# Energy_Monitor.net
KiCad netlist of a schematic drawn in Altium Designer
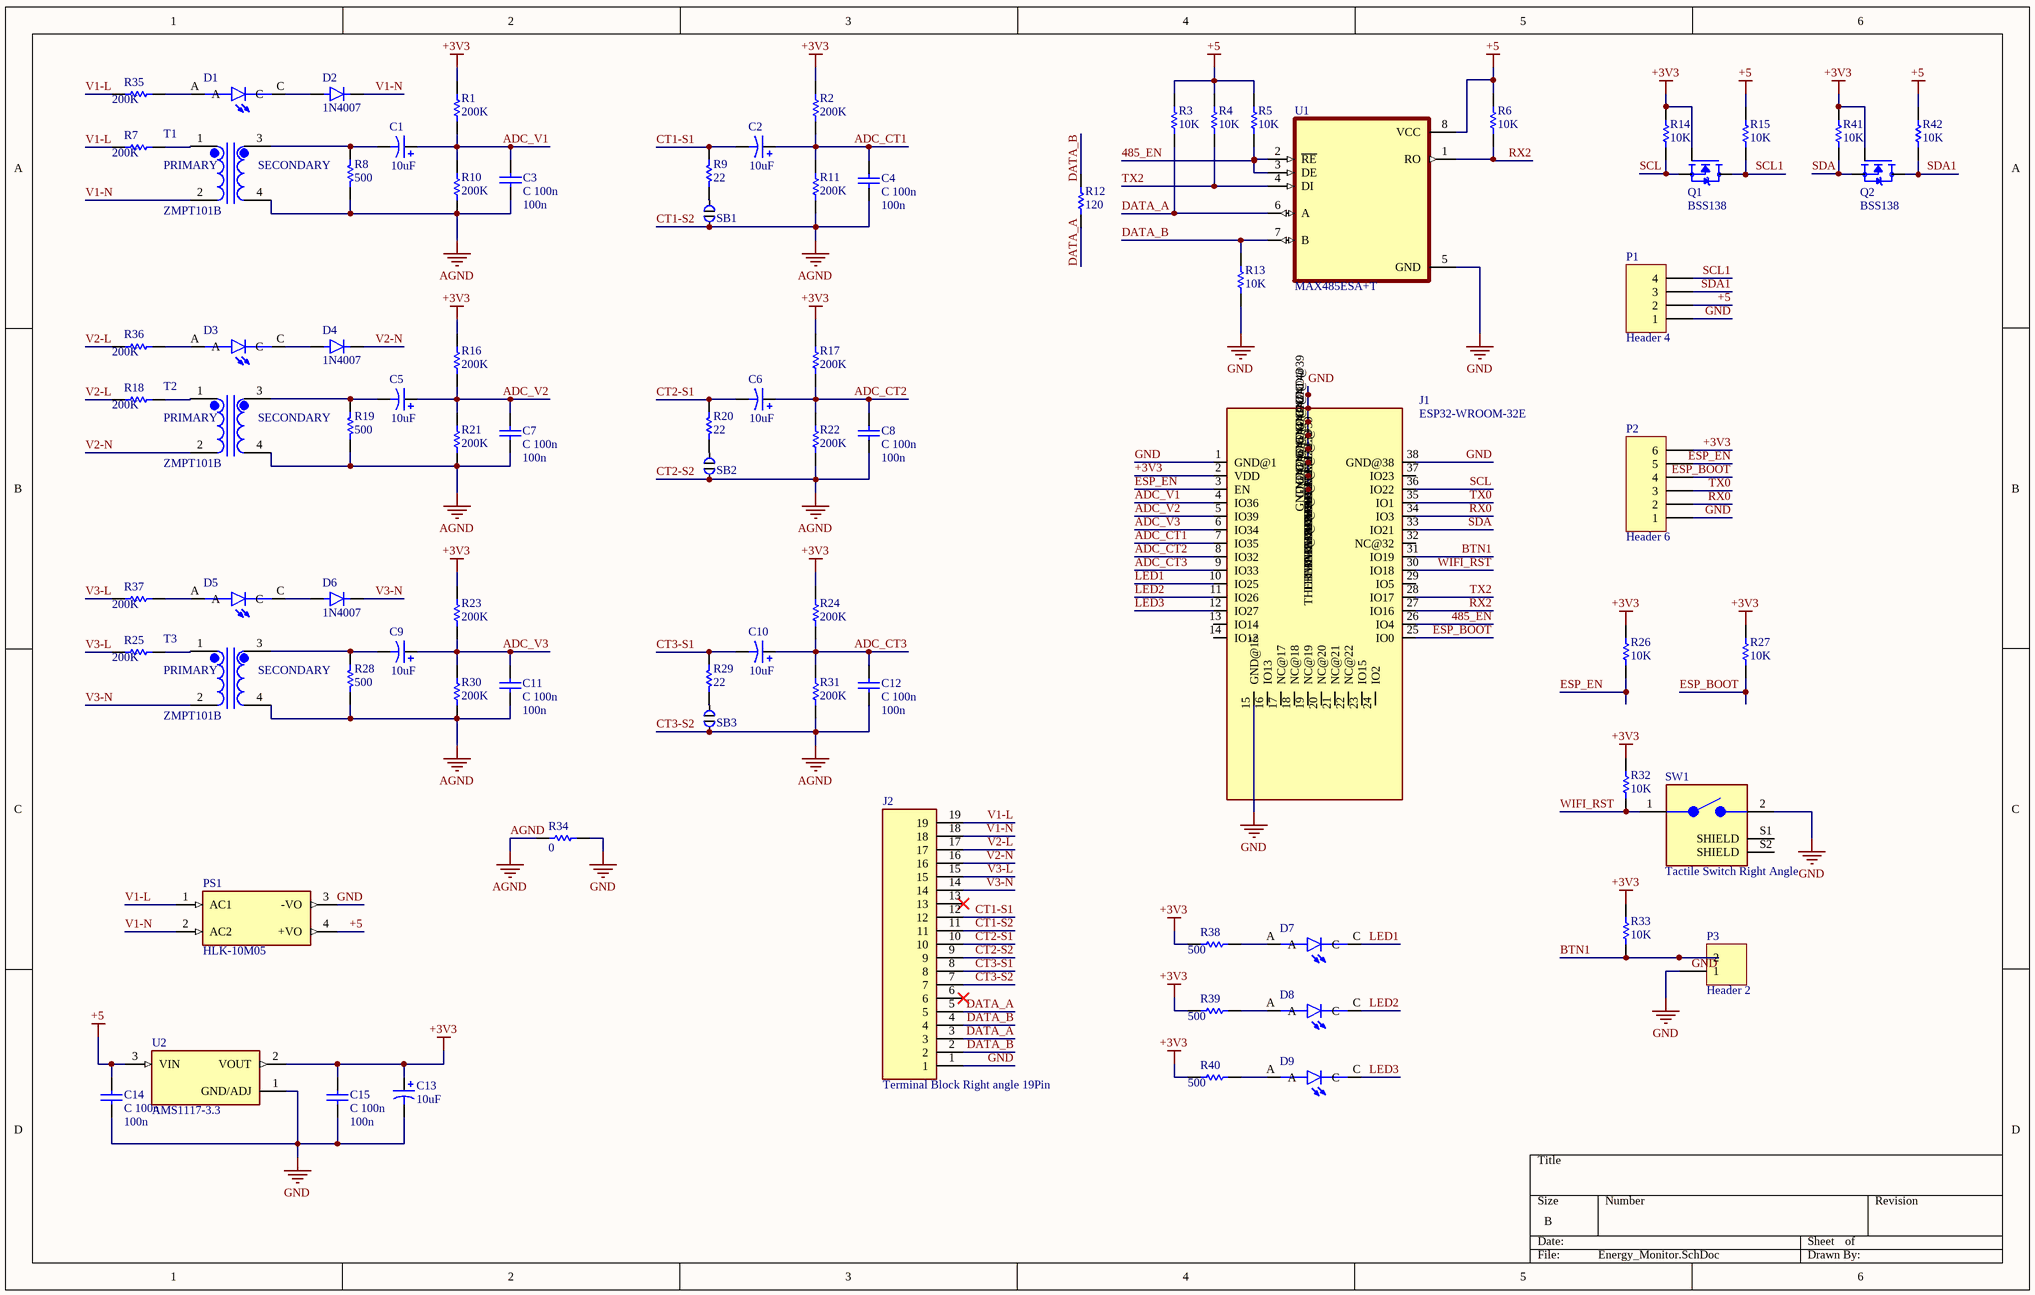
[diagram p0: Energy_Monitor.SchDoc]

(export (version "E")
  (design (tool "Eeschema 10.0.6"))
  (components
    (comp (ref "C1")
      (value "10uF")
      (footprint "C1206")
      (description "Polarized Capacitor (Radial)")
      (fields (field (name "Comment") "C Tantalum 10u") (field (name "PUBLISHER") "Altium Limited"))
      (libsource (lib "Miscellaneous Devices") (part "Cap Pol1"))
    )
    (comp (ref "C2")
      (value "10uF")
      (footprint "C1206")
      (description "Polarized Capacitor (Radial)")
      (fields (field (name "Comment") "C Tantalum 10u") (field (name "PUBLISHER") "Altium Limited"))
      (libsource (lib "Miscellaneous Devices") (part "Cap Pol1"))
    )
    (comp (ref "C3")
      (value "C 100n")
      (footprint "6-0805_N")
      (description "Capacitor")
      (fields (field (name "ALTIUM_VALUE") "100n") (field (name "PUBLISHER") "Altium Limited"))
      (libsource (lib "Miscellaneous Devices") (part "Cap"))
    )
    (comp (ref "C4")
      (value "C 100n")
      (footprint "6-0805_N")
      (description "Capacitor")
      (fields (field (name "ALTIUM_VALUE") "100n") (field (name "PUBLISHER") "Altium Limited"))
      (libsource (lib "Miscellaneous Devices") (part "Cap"))
    )
    (comp (ref "C5")
      (value "10uF")
      (footprint "C1206")
      (description "Polarized Capacitor (Radial)")
      (fields (field (name "Comment") "C Tantalum 10u") (field (name "PUBLISHER") "Altium Limited"))
      (libsource (lib "Miscellaneous Devices") (part "Cap Pol1"))
    )
    (comp (ref "C6")
      (value "10uF")
      (footprint "C1206")
      (description "Polarized Capacitor (Radial)")
      (fields (field (name "Comment") "C Tantalum 10u") (field (name "PUBLISHER") "Altium Limited"))
      (libsource (lib "Miscellaneous Devices") (part "Cap Pol1"))
    )
    (comp (ref "C7")
      (value "C 100n")
      (footprint "6-0805_N")
      (description "Capacitor")
      (fields (field (name "ALTIUM_VALUE") "100n") (field (name "PUBLISHER") "Altium Limited"))
      (libsource (lib "Miscellaneous Devices") (part "Cap"))
    )
    (comp (ref "C8")
      (value "C 100n")
      (footprint "6-0805_N")
      (description "Capacitor")
      (fields (field (name "ALTIUM_VALUE") "100n") (field (name "PUBLISHER") "Altium Limited"))
      (libsource (lib "Miscellaneous Devices") (part "Cap"))
    )
    (comp (ref "C9")
      (value "10uF")
      (footprint "C1206")
      (description "Polarized Capacitor (Radial)")
      (fields (field (name "Comment") "C Tantalum 10u") (field (name "PUBLISHER") "Altium Limited"))
      (libsource (lib "Miscellaneous Devices") (part "Cap Pol1"))
    )
    (comp (ref "C10")
      (value "10uF")
      (footprint "C1206")
      (description "Polarized Capacitor (Radial)")
      (fields (field (name "Comment") "C Tantalum 10u") (field (name "PUBLISHER") "Altium Limited"))
      (libsource (lib "Miscellaneous Devices") (part "Cap Pol1"))
    )
    (comp (ref "C11")
      (value "C 100n")
      (footprint "6-0805_N")
      (description "Capacitor")
      (fields (field (name "ALTIUM_VALUE") "100n") (field (name "PUBLISHER") "Altium Limited"))
      (libsource (lib "Miscellaneous Devices") (part "Cap"))
    )
    (comp (ref "C12")
      (value "C 100n")
      (footprint "6-0805_N")
      (description "Capacitor")
      (fields (field (name "ALTIUM_VALUE") "100n") (field (name "PUBLISHER") "Altium Limited"))
      (libsource (lib "Miscellaneous Devices") (part "Cap"))
    )
    (comp (ref "C13")
      (value "10uF")
      (footprint "C1206")
      (description "Polarized Capacitor (Radial)")
      (fields (field (name "Comment") "C Tantalum 10u") (field (name "PUBLISHER") "Altium Limited"))
      (libsource (lib "Miscellaneous Devices") (part "Cap Pol1"))
    )
    (comp (ref "C14")
      (value "C 100n")
      (footprint "6-0805_N")
      (description "Capacitor")
      (fields (field (name "ALTIUM_VALUE") "100n") (field (name "PUBLISHER") "Altium Limited"))
      (libsource (lib "Miscellaneous Devices") (part "Cap"))
    )
    (comp (ref "C15")
      (value "C 100n")
      (footprint "6-0805_N")
      (description "Capacitor")
      (fields (field (name "ALTIUM_VALUE") "100n") (field (name "PUBLISHER") "Altium Limited"))
      (libsource (lib "Miscellaneous Devices") (part "Cap"))
    )
    (comp (ref "D1")
      (value "LED 0805")
      (footprint "LEDC2012X70N")
      (description "LED Uni-Color Green 4-Pin Chip 0805 T/R")
      (fields (field (name "MP") "597-3305-607F"))
      (libsource (lib "597-3305-607F") (part "597-3305-607F"))
    )
    (comp (ref "D2")
      (value "1N4007")
      (footprint "DIOM5227X270N")
      (description "Diode Standard 1000 V 1A Surface Mount DO-214AC (SMA)")
      (fields (field (name "MF") "Diotec Semiconductor") (field (name "MP") "S1M"))
      (libsource (lib "S1M") (part "S1M"))
    )
    (comp (ref "D3")
      (value "LED 0805")
      (footprint "LEDC2012X70N")
      (description "LED Uni-Color Green 4-Pin Chip 0805 T/R")
      (fields (field (name "MP") "597-3305-607F"))
      (libsource (lib "597-3305-607F") (part "597-3305-607F"))
    )
    (comp (ref "D4")
      (value "1N4007")
      (footprint "DIOM5227X270N")
      (description "Diode Standard 1000 V 1A Surface Mount DO-214AC (SMA)")
      (fields (field (name "MF") "Diotec Semiconductor") (field (name "MP") "S1M"))
      (libsource (lib "S1M") (part "S1M"))
    )
    (comp (ref "D5")
      (value "LED 0805")
      (footprint "LEDC2012X70N")
      (description "LED Uni-Color Green 4-Pin Chip 0805 T/R")
      (fields (field (name "MP") "597-3305-607F"))
      (libsource (lib "597-3305-607F") (part "597-3305-607F"))
    )
    (comp (ref "D6")
      (value "1N4007")
      (footprint "DIOM5227X270N")
      (description "Diode Standard 1000 V 1A Surface Mount DO-214AC (SMA)")
      (fields (field (name "MF") "Diotec Semiconductor") (field (name "MP") "S1M"))
      (libsource (lib "S1M") (part "S1M"))
    )
    (comp (ref "D7")
      (value "LED 0805")
      (footprint "LEDC2012X70N")
      (description "LED Uni-Color Green 4-Pin Chip 0805 T/R")
      (fields (field (name "MP") "597-3305-607F"))
      (libsource (lib "597-3305-607F") (part "597-3305-607F"))
    )
    (comp (ref "D8")
      (value "LED 0805")
      (footprint "LEDC2012X70N")
      (description "LED Uni-Color Green 4-Pin Chip 0805 T/R")
      (fields (field (name "MP") "597-3305-607F"))
      (libsource (lib "597-3305-607F") (part "597-3305-607F"))
    )
    (comp (ref "D9")
      (value "LED 0805")
      (footprint "LEDC2012X70N")
      (description "LED Uni-Color Green 4-Pin Chip 0805 T/R")
      (fields (field (name "MP") "597-3305-607F"))
      (libsource (lib "597-3305-607F") (part "597-3305-607F"))
    )
    (comp (ref "J1")
      (value "ESP32-WROOM-32E")
      (footprint "ESP32-WROOM-32E")
      (fields (field (name "MF") "Espressif Systems"))
      (libsource (lib "ESP32-WROOM-32E") (part "ESP32-WROOM-32E"))
    )
    (comp (ref "J2")
      (value "Terminal Block Right angle 19Pin")
      (footprint "CUI_TBP01R1-508-19BE")
      (fields (field (name "MP") "TBP01R1-508-19BE"))
      (libsource (lib "TBP01R1-508-19BE") (part "TBP01R1-508-19BE"))
    )
    (comp (ref "P1")
      (value "Header 4")
      (footprint "JST_B4B-XH-A(LF)(SN)")
      (description "Header, 4-Pin")
      (fields (field (name "PUBLISHER") "Altium Limited"))
      (libsource (lib "Miscellaneous Connectors") (part "Header 4"))
    )
    (comp (ref "P2")
      (value "Header 6")
      (footprint "HDR1X6")
      (description "Header, 6-Pin")
      (fields (field (name "PUBLISHER") "Altium Limited"))
      (libsource (lib "Miscellaneous Connectors") (part "Header 6"))
    )
    (comp (ref "P3")
      (value "Header 2")
      (footprint "HDR1X2")
      (description "Header, 2-Pin")
      (fields (field (name "PUBLISHER") "Altium Limited"))
      (libsource (lib "Miscellaneous Connectors") (part "Header 2"))
    )
    (comp (ref "PS1")
      (value "HLK-10M05")
      (footprint "CONV_HLK-10M05")
      (description "10W Ultra-Compact Power Module")
      (fields (field (name "MF") "Hi-link"))
      (libsource (lib "HLK-10M05") (part "HLK-10M05"))
    )
    (comp (ref "Q1")
      (value "BSS138")
      (footprint "SOT95P240X111-3N")
      (description "N-Channel 50V 220mA (Ta) 360mW (Ta) Surface Mount SOT-23-3")
      (fields (field (name "MF") "ON Semiconductor"))
      (libsource (lib "BSS138") (part "BSS138"))
    )
    (comp (ref "Q2")
      (value "BSS138")
      (footprint "SOT95P240X111-3N")
      (description "N-Channel 50V 220mA (Ta) 360mW (Ta) Surface Mount SOT-23-3")
      (fields (field (name "MF") "ON Semiconductor"))
      (libsource (lib "BSS138") (part "BSS138"))
    )
    (comp (ref "R1")
      (value "200K")
      (footprint "6-0805_N")
      (description "Resistor")
      (fields (field (name "Comment") "R 200K") (field (name "PUBLISHER") "Altium Limited"))
      (libsource (lib "Miscellaneous Devices") (part "Res1"))
    )
    (comp (ref "R2")
      (value "200K")
      (footprint "6-0805_N")
      (description "Resistor")
      (fields (field (name "Comment") "R 200K") (field (name "PUBLISHER") "Altium Limited"))
      (libsource (lib "Miscellaneous Devices") (part "Res1"))
    )
    (comp (ref "R3")
      (value "10K")
      (footprint "6-0805_N")
      (description "Resistor")
      (fields (field (name "Comment") "R 10K") (field (name "PUBLISHER") "Altium Limited"))
      (libsource (lib "Miscellaneous Devices") (part "Res1"))
    )
    (comp (ref "R4")
      (value "10K")
      (footprint "6-0805_N")
      (description "Resistor")
      (fields (field (name "Comment") "R 10K") (field (name "PUBLISHER") "Altium Limited"))
      (libsource (lib "Miscellaneous Devices") (part "Res1"))
    )
    (comp (ref "R5")
      (value "10K")
      (footprint "6-0805_N")
      (description "Resistor")
      (fields (field (name "Comment") "R 10K") (field (name "PUBLISHER") "Altium Limited"))
      (libsource (lib "Miscellaneous Devices") (part "Res1"))
    )
    (comp (ref "R6")
      (value "10K")
      (footprint "6-0805_N")
      (description "Resistor")
      (fields (field (name "Comment") "R 10K") (field (name "PUBLISHER") "Altium Limited"))
      (libsource (lib "Miscellaneous Devices") (part "Res1"))
    )
    (comp (ref "R7")
      (value "200K")
      (footprint "6-0805_N")
      (description "Resistor")
      (fields (field (name "Comment") "R 200K") (field (name "PUBLISHER") "Altium Limited"))
      (libsource (lib "Miscellaneous Devices") (part "Res1"))
    )
    (comp (ref "R8")
      (value "500")
      (footprint "6-0805_N")
      (description "Resistor")
      (fields (field (name "Comment") "R 500") (field (name "PUBLISHER") "Altium Limited"))
      (libsource (lib "Miscellaneous Devices") (part "Res1"))
    )
    (comp (ref "R9")
      (value "22")
      (footprint "6-0805_N")
      (description "Resistor")
      (fields (field (name "Comment") "R 22") (field (name "PUBLISHER") "Altium Limited"))
      (libsource (lib "Miscellaneous Devices") (part "Res1"))
    )
    (comp (ref "R10")
      (value "200K")
      (footprint "6-0805_N")
      (description "Resistor")
      (fields (field (name "Comment") "R 200K") (field (name "PUBLISHER") "Altium Limited"))
      (libsource (lib "Miscellaneous Devices") (part "Res1"))
    )
    (comp (ref "R11")
      (value "200K")
      (footprint "6-0805_N")
      (description "Resistor")
      (fields (field (name "Comment") "R 200K") (field (name "PUBLISHER") "Altium Limited"))
      (libsource (lib "Miscellaneous Devices") (part "Res1"))
    )
    (comp (ref "R12")
      (value "120")
      (footprint "6-0805_N")
      (description "Resistor")
      (fields (field (name "Comment") "R 120") (field (name "PUBLISHER") "Altium Limited"))
      (libsource (lib "Miscellaneous Devices") (part "Res1"))
    )
    (comp (ref "R13")
      (value "10K")
      (footprint "6-0805_N")
      (description "Resistor")
      (fields (field (name "Comment") "R 10K") (field (name "PUBLISHER") "Altium Limited"))
      (libsource (lib "Miscellaneous Devices") (part "Res1"))
    )
    (comp (ref "R14")
      (value "10K")
      (footprint "6-0805_N")
      (description "Resistor")
      (fields (field (name "Comment") "R 10K") (field (name "PUBLISHER") "Altium Limited"))
      (libsource (lib "Miscellaneous Devices") (part "Res1"))
    )
    (comp (ref "R15")
      (value "10K")
      (footprint "6-0805_N")
      (description "Resistor")
      (fields (field (name "Comment") "R 10K") (field (name "PUBLISHER") "Altium Limited"))
      (libsource (lib "Miscellaneous Devices") (part "Res1"))
    )
    (comp (ref "R16")
      (value "200K")
      (footprint "6-0805_N")
      (description "Resistor")
      (fields (field (name "Comment") "R 200K") (field (name "PUBLISHER") "Altium Limited"))
      (libsource (lib "Miscellaneous Devices") (part "Res1"))
    )
    (comp (ref "R17")
      (value "200K")
      (footprint "6-0805_N")
      (description "Resistor")
      (fields (field (name "Comment") "R 200K") (field (name "PUBLISHER") "Altium Limited"))
      (libsource (lib "Miscellaneous Devices") (part "Res1"))
    )
    (comp (ref "R18")
      (value "200K")
      (footprint "6-0805_N")
      (description "Resistor")
      (fields (field (name "Comment") "R 200K") (field (name "PUBLISHER") "Altium Limited"))
      (libsource (lib "Miscellaneous Devices") (part "Res1"))
    )
    (comp (ref "R19")
      (value "500")
      (footprint "6-0805_N")
      (description "Resistor")
      (fields (field (name "Comment") "R 500") (field (name "PUBLISHER") "Altium Limited"))
      (libsource (lib "Miscellaneous Devices") (part "Res1"))
    )
    (comp (ref "R20")
      (value "22")
      (footprint "6-0805_N")
      (description "Resistor")
      (fields (field (name "Comment") "R 22") (field (name "PUBLISHER") "Altium Limited"))
      (libsource (lib "Miscellaneous Devices") (part "Res1"))
    )
    (comp (ref "R21")
      (value "200K")
      (footprint "6-0805_N")
      (description "Resistor")
      (fields (field (name "Comment") "R 200K") (field (name "PUBLISHER") "Altium Limited"))
      (libsource (lib "Miscellaneous Devices") (part "Res1"))
    )
    (comp (ref "R22")
      (value "200K")
      (footprint "6-0805_N")
      (description "Resistor")
      (fields (field (name "Comment") "R 200K") (field (name "PUBLISHER") "Altium Limited"))
      (libsource (lib "Miscellaneous Devices") (part "Res1"))
    )
    (comp (ref "R23")
      (value "200K")
      (footprint "6-0805_N")
      (description "Resistor")
      (fields (field (name "Comment") "R 200K") (field (name "PUBLISHER") "Altium Limited"))
      (libsource (lib "Miscellaneous Devices") (part "Res1"))
    )
    (comp (ref "R24")
      (value "200K")
      (footprint "6-0805_N")
      (description "Resistor")
      (fields (field (name "Comment") "R 200K") (field (name "PUBLISHER") "Altium Limited"))
      (libsource (lib "Miscellaneous Devices") (part "Res1"))
    )
    (comp (ref "R25")
      (value "200K")
      (footprint "6-0805_N")
      (description "Resistor")
      (fields (field (name "Comment") "R 200K") (field (name "PUBLISHER") "Altium Limited"))
      (libsource (lib "Miscellaneous Devices") (part "Res1"))
    )
    (comp (ref "R26")
      (value "10K")
      (footprint "6-0805_N")
      (description "Resistor")
      (fields (field (name "Comment") "R 10K") (field (name "PUBLISHER") "Altium Limited"))
      (libsource (lib "Miscellaneous Devices") (part "Res1"))
    )
    (comp (ref "R27")
      (value "10K")
      (footprint "6-0805_N")
      (description "Resistor")
      (fields (field (name "Comment") "R 10K") (field (name "PUBLISHER") "Altium Limited"))
      (libsource (lib "Miscellaneous Devices") (part "Res1"))
    )
    (comp (ref "R28")
      (value "500")
      (footprint "6-0805_N")
      (description "Resistor")
      (fields (field (name "Comment") "R 500") (field (name "PUBLISHER") "Altium Limited"))
      (libsource (lib "Miscellaneous Devices") (part "Res1"))
    )
    (comp (ref "R29")
      (value "22")
      (footprint "6-0805_N")
      (description "Resistor")
      (fields (field (name "Comment") "R 22") (field (name "PUBLISHER") "Altium Limited"))
      (libsource (lib "Miscellaneous Devices") (part "Res1"))
    )
    (comp (ref "R30")
      (value "200K")
      (footprint "6-0805_N")
      (description "Resistor")
      (fields (field (name "Comment") "R 200K") (field (name "PUBLISHER") "Altium Limited"))
      (libsource (lib "Miscellaneous Devices") (part "Res1"))
    )
    (comp (ref "R31")
      (value "200K")
      (footprint "6-0805_N")
      (description "Resistor")
      (fields (field (name "Comment") "R 200K") (field (name "PUBLISHER") "Altium Limited"))
      (libsource (lib "Miscellaneous Devices") (part "Res1"))
    )
    (comp (ref "R32")
      (value "10K")
      (footprint "6-0805_N")
      (description "Resistor")
      (fields (field (name "Comment") "R 10K") (field (name "PUBLISHER") "Altium Limited"))
      (libsource (lib "Miscellaneous Devices") (part "Res1"))
    )
    (comp (ref "R33")
      (value "10K")
      (footprint "6-0805_N")
      (description "Resistor")
      (fields (field (name "Comment") "R 10K") (field (name "PUBLISHER") "Altium Limited"))
      (libsource (lib "Miscellaneous Devices") (part "Res1"))
    )
    (comp (ref "R34")
      (value "0")
      (footprint "6-0805_N")
      (description "Resistor")
      (fields (field (name "Comment") "R 0") (field (name "PUBLISHER") "Altium Limited"))
      (libsource (lib "Miscellaneous Devices") (part "Res1"))
    )
    (comp (ref "R35")
      (value "200K")
      (footprint "6-0805_N")
      (description "Resistor")
      (fields (field (name "Comment") "R 200K") (field (name "PUBLISHER") "Altium Limited"))
      (libsource (lib "Miscellaneous Devices") (part "Res1"))
    )
    (comp (ref "R36")
      (value "200K")
      (footprint "6-0805_N")
      (description "Resistor")
      (fields (field (name "Comment") "R 200K") (field (name "PUBLISHER") "Altium Limited"))
      (libsource (lib "Miscellaneous Devices") (part "Res1"))
    )
    (comp (ref "R37")
      (value "200K")
      (footprint "6-0805_N")
      (description "Resistor")
      (fields (field (name "Comment") "R 200K") (field (name "PUBLISHER") "Altium Limited"))
      (libsource (lib "Miscellaneous Devices") (part "Res1"))
    )
    (comp (ref "R38")
      (value "500")
      (footprint "6-0805_N")
      (description "Resistor")
      (fields (field (name "Comment") "R 500") (field (name "PUBLISHER") "Altium Limited"))
      (libsource (lib "Miscellaneous Devices") (part "Res1"))
    )
    (comp (ref "R39")
      (value "500")
      (footprint "6-0805_N")
      (description "Resistor")
      (fields (field (name "Comment") "R 500") (field (name "PUBLISHER") "Altium Limited"))
      (libsource (lib "Miscellaneous Devices") (part "Res1"))
    )
    (comp (ref "R40")
      (value "500")
      (footprint "6-0805_N")
      (description "Resistor")
      (fields (field (name "Comment") "R 500") (field (name "PUBLISHER") "Altium Limited"))
      (libsource (lib "Miscellaneous Devices") (part "Res1"))
    )
    (comp (ref "R41")
      (value "10K")
      (footprint "6-0805_N")
      (description "Resistor")
      (fields (field (name "Comment") "R 10K") (field (name "PUBLISHER") "Altium Limited"))
      (libsource (lib "Miscellaneous Devices") (part "Res1"))
    )
    (comp (ref "R42")
      (value "10K")
      (footprint "6-0805_N")
      (description "Resistor")
      (fields (field (name "Comment") "R 10K") (field (name "PUBLISHER") "Altium Limited"))
      (libsource (lib "Miscellaneous Devices") (part "Res1"))
    )
    (comp (ref "SB1")
      (value "solder Bridge")
      (footprint "Solder Bridge")
      (libsource (lib "solder bridge") (part "solder Bridge"))
    )
    (comp (ref "SB2")
      (value "solder Bridge")
      (footprint "Solder Bridge")
      (libsource (lib "solder bridge") (part "solder Bridge"))
    )
    (comp (ref "SB3")
      (value "solder Bridge")
      (footprint "Solder Bridge")
      (libsource (lib "solder bridge") (part "solder Bridge"))
    )
    (comp (ref "SW1")
      (value "Tactile Switch Right Angle")
      (footprint "SW_1825027-5")
      (description "Switch Tactile OFF (ON) SPST Round Button PC Pins 0.05A 24VDC 1.57N Thru-Hole Loose Piece")
      (fields (field (name "MP") "1825027-5") (field (name "MF") "TE Connectivity"))
      (libsource (lib "1825027-5") (part "1825027-5"))
    )
    (comp (ref "T1")
      (value "ZMPT101B")
      (footprint "XFMR_ZMPT101B")
      (description "Current-type Voltage Transformer")
      (fields (field (name "MF") "Qingxian Zeming Langxi Electronic"))
      (libsource (lib "ZMPT101B") (part "ZMPT101B"))
    )
    (comp (ref "T2")
      (value "ZMPT101B")
      (footprint "XFMR_ZMPT101B")
      (description "Current-type Voltage Transformer")
      (fields (field (name "MF") "Qingxian Zeming Langxi Electronic"))
      (libsource (lib "ZMPT101B") (part "ZMPT101B"))
    )
    (comp (ref "T3")
      (value "ZMPT101B")
      (footprint "XFMR_ZMPT101B")
      (description "Current-type Voltage Transformer")
      (fields (field (name "MF") "Qingxian Zeming Langxi Electronic"))
      (libsource (lib "ZMPT101B") (part "ZMPT101B"))
    )
    (comp (ref "U1")
      (value "MAX485ESA+T")
      (footprint "SOIC127P600X175-8N")
      (description "1/1 Transceiver Half RS422, RS485 8-SOIC")
      (fields (field (name "MP") "MAX485ESA") (field (name "MF") "Maxim Integrated"))
      (libsource (lib "MAX485ESA_T") (part "MAX485ESA+T"))
    )
    (comp (ref "U2")
      (value "AMS1117-3.3")
      (footprint "SOT229P700X180-4N")
      (description "Sot223/Pkg 1-Amp 3.3-Volt Low Drop Out Voltage Regulatator")
      (fields (field (name "MF") "Advanced Monolithic Systems"))
      (libsource (lib "AMS1117-3.3") (part "AMS1117-3.3"))
    )
  )
  (nets
    (net (code "1") (name "+3V3") (class "Default")
      (node (ref "C13") (pin "1") (pinfunction "1_1") (pintype "passive"))
      (node (ref "C15") (pin "2") (pinfunction "2_2") (pintype "passive"))
      (node (ref "J1") (pin "2") (pinfunction "VDD_2") (pintype "bidirectional"))
      (node (ref "P2") (pin "6") (pinfunction "6_6") (pintype "passive"))
      (node (ref "Q1") (pin "1") (pinfunction "G_1") (pintype "passive"))
      (node (ref "Q2") (pin "1") (pinfunction "G_1") (pintype "passive"))
      (node (ref "R1") (pin "2") (pinfunction "2_2") (pintype "passive"))
      (node (ref "R14") (pin "2") (pinfunction "2_2") (pintype "passive"))
      (node (ref "R16") (pin "2") (pinfunction "2_2") (pintype "passive"))
      (node (ref "R17") (pin "2") (pinfunction "2_2") (pintype "passive"))
      (node (ref "R2") (pin "2") (pinfunction "2_2") (pintype "passive"))
      (node (ref "R23") (pin "2") (pinfunction "2_2") (pintype "passive"))
      (node (ref "R24") (pin "2") (pinfunction "2_2") (pintype "passive"))
      (node (ref "R26") (pin "2") (pinfunction "2_2") (pintype "passive"))
      (node (ref "R27") (pin "2") (pinfunction "2_2") (pintype "passive"))
      (node (ref "R32") (pin "2") (pinfunction "2_2") (pintype "passive"))
      (node (ref "R33") (pin "2") (pinfunction "2_2") (pintype "passive"))
      (node (ref "R38") (pin "1") (pinfunction "1_1") (pintype "passive"))
      (node (ref "R39") (pin "1") (pinfunction "1_1") (pintype "passive"))
      (node (ref "R40") (pin "1") (pinfunction "1_1") (pintype "passive"))
      (node (ref "R41") (pin "2") (pinfunction "2_2") (pintype "passive"))
      (node (ref "U2") (pin "2") (pinfunction "VOUT_2") (pintype "output"))
    )
    (net (code "2") (name "+5") (class "Default")
      (node (ref "C14") (pin "2") (pinfunction "2_2") (pintype "passive"))
      (node (ref "P1") (pin "2") (pinfunction "2_2") (pintype "passive"))
      (node (ref "PS1") (pin "4") (pinfunction "+VO_4") (pintype "output"))
      (node (ref "R15") (pin "2") (pinfunction "2_2") (pintype "passive"))
      (node (ref "R3") (pin "2") (pinfunction "2_2") (pintype "passive"))
      (node (ref "R4") (pin "2") (pinfunction "2_2") (pintype "passive"))
      (node (ref "R42") (pin "2") (pinfunction "2_2") (pintype "passive"))
      (node (ref "R5") (pin "2") (pinfunction "2_2") (pintype "passive"))
      (node (ref "R6") (pin "2") (pinfunction "2_2") (pintype "passive"))
      (node (ref "U1") (pin "8") (pinfunction "VCC_8") (pintype "power_in"))
      (node (ref "U2") (pin "3") (pinfunction "VIN_3") (pintype "input"))
    )
    (net (code "3") (name "/485_EN") (class "Default")
      (node (ref "J1") (pin "26") (pinfunction "IO4_26") (pintype "bidirectional"))
      (node (ref "R5") (pin "1") (pinfunction "1_1") (pintype "passive"))
      (node (ref "U1") (pin "2") (pinfunction "~{RE}_2") (pintype "input"))
      (node (ref "U1") (pin "3") (pinfunction "DE_3") (pintype "input"))
    )
    (net (code "4") (name "/ADC_CT1") (class "Default")
      (node (ref "C2") (pin "1") (pinfunction "1_1") (pintype "passive"))
      (node (ref "C4") (pin "2") (pinfunction "2_2") (pintype "passive"))
      (node (ref "J1") (pin "7") (pinfunction "IO35_7") (pintype "bidirectional"))
      (node (ref "R11") (pin "2") (pinfunction "2_2") (pintype "passive"))
      (node (ref "R2") (pin "1") (pinfunction "1_1") (pintype "passive"))
    )
    (net (code "5") (name "/ADC_CT2") (class "Default")
      (node (ref "C6") (pin "1") (pinfunction "1_1") (pintype "passive"))
      (node (ref "C8") (pin "2") (pinfunction "2_2") (pintype "passive"))
      (node (ref "J1") (pin "8") (pinfunction "IO32_8") (pintype "bidirectional"))
      (node (ref "R17") (pin "1") (pinfunction "1_1") (pintype "passive"))
      (node (ref "R22") (pin "2") (pinfunction "2_2") (pintype "passive"))
    )
    (net (code "6") (name "/ADC_CT3") (class "Default")
      (node (ref "C10") (pin "1") (pinfunction "1_1") (pintype "passive"))
      (node (ref "C12") (pin "2") (pinfunction "2_2") (pintype "passive"))
      (node (ref "J1") (pin "9") (pinfunction "IO33_9") (pintype "bidirectional"))
      (node (ref "R24") (pin "1") (pinfunction "1_1") (pintype "passive"))
      (node (ref "R31") (pin "2") (pinfunction "2_2") (pintype "passive"))
    )
    (net (code "7") (name "/ADC_V1") (class "Default")
      (node (ref "C1") (pin "1") (pinfunction "1_1") (pintype "passive"))
      (node (ref "C3") (pin "2") (pinfunction "2_2") (pintype "passive"))
      (node (ref "J1") (pin "4") (pinfunction "IO36_4") (pintype "bidirectional"))
      (node (ref "R1") (pin "1") (pinfunction "1_1") (pintype "passive"))
      (node (ref "R10") (pin "2") (pinfunction "2_2") (pintype "passive"))
    )
    (net (code "8") (name "/ADC_V2") (class "Default")
      (node (ref "C5") (pin "1") (pinfunction "1_1") (pintype "passive"))
      (node (ref "C7") (pin "2") (pinfunction "2_2") (pintype "passive"))
      (node (ref "J1") (pin "5") (pinfunction "IO39_5") (pintype "bidirectional"))
      (node (ref "R16") (pin "1") (pinfunction "1_1") (pintype "passive"))
      (node (ref "R21") (pin "2") (pinfunction "2_2") (pintype "passive"))
    )
    (net (code "9") (name "/ADC_V3") (class "Default")
      (node (ref "C11") (pin "2") (pinfunction "2_2") (pintype "passive"))
      (node (ref "C9") (pin "1") (pinfunction "1_1") (pintype "passive"))
      (node (ref "J1") (pin "6") (pinfunction "IO34_6") (pintype "bidirectional"))
      (node (ref "R23") (pin "1") (pinfunction "1_1") (pintype "passive"))
      (node (ref "R30") (pin "2") (pinfunction "2_2") (pintype "passive"))
    )
    (net (code "10") (name "/BTN1") (class "Default")
      (node (ref "J1") (pin "31") (pinfunction "IO19_31") (pintype "bidirectional"))
      (node (ref "P3") (pin "2") (pinfunction "2_2") (pintype "passive"))
      (node (ref "R33") (pin "1") (pinfunction "1_1") (pintype "passive"))
    )
    (net (code "11") (name "/CT1-S1") (class "Default")
      (node (ref "C2") (pin "2") (pinfunction "2_2") (pintype "passive"))
      (node (ref "J2") (pin "12") (pinfunction "12_12") (pintype "passive"))
      (node (ref "R9") (pin "2") (pinfunction "2_2") (pintype "passive"))
    )
    (net (code "12") (name "/CT2-S1") (class "Default")
      (node (ref "C6") (pin "2") (pinfunction "2_2") (pintype "passive"))
      (node (ref "J2") (pin "10") (pinfunction "10_10") (pintype "passive"))
      (node (ref "R20") (pin "2") (pinfunction "2_2") (pintype "passive"))
    )
    (net (code "13") (name "/CT3-S1") (class "Default")
      (node (ref "C10") (pin "2") (pinfunction "2_2") (pintype "passive"))
      (node (ref "J2") (pin "8") (pinfunction "8_8") (pintype "passive"))
      (node (ref "R29") (pin "2") (pinfunction "2_2") (pintype "passive"))
    )
    (net (code "14") (name "/DATA_A") (class "Default")
      (node (ref "J2") (pin "3") (pinfunction "3_3") (pintype "passive"))
      (node (ref "J2") (pin "5") (pinfunction "5_5") (pintype "passive"))
      (node (ref "R12") (pin "2") (pinfunction "2_2") (pintype "passive"))
      (node (ref "R3") (pin "1") (pinfunction "1_1") (pintype "passive"))
      (node (ref "U1") (pin "6") (pinfunction "A_6") (pintype "bidirectional"))
    )
    (net (code "15") (name "/DATA_B") (class "Default")
      (node (ref "J2") (pin "2") (pinfunction "2_2") (pintype "passive"))
      (node (ref "J2") (pin "4") (pinfunction "4_4") (pintype "passive"))
      (node (ref "R12") (pin "1") (pinfunction "1_1") (pintype "passive"))
      (node (ref "R13") (pin "2") (pinfunction "2_2") (pintype "passive"))
      (node (ref "U1") (pin "7") (pinfunction "B_7") (pintype "bidirectional"))
    )
    (net (code "16") (name "/ESP_BOOT") (class "Default")
      (node (ref "J1") (pin "25") (pinfunction "IO0_25") (pintype "bidirectional"))
      (node (ref "P2") (pin "4") (pinfunction "4_4") (pintype "passive"))
      (node (ref "R27") (pin "1") (pinfunction "1_1") (pintype "passive"))
    )
    (net (code "17") (name "/ESP_EN") (class "Default")
      (node (ref "J1") (pin "3") (pinfunction "EN_3") (pintype "bidirectional"))
      (node (ref "P2") (pin "5") (pinfunction "5_5") (pintype "passive"))
      (node (ref "R26") (pin "1") (pinfunction "1_1") (pintype "passive"))
    )
    (net (code "18") (name "/LED1") (class "Default")
      (node (ref "D7") (pin "C") (pinfunction "C_C") (pintype "passive"))
      (node (ref "J1") (pin "10") (pinfunction "IO25_10") (pintype "bidirectional"))
    )
    (net (code "19") (name "/LED2") (class "Default")
      (node (ref "D8") (pin "C") (pinfunction "C_C") (pintype "passive"))
      (node (ref "J1") (pin "11") (pinfunction "IO26_11") (pintype "bidirectional"))
    )
    (net (code "20") (name "/LED3") (class "Default")
      (node (ref "D9") (pin "C") (pinfunction "C_C") (pintype "passive"))
      (node (ref "J1") (pin "12") (pinfunction "IO27_12") (pintype "bidirectional"))
    )
    (net (code "21") (name "/RX0") (class "Default")
      (node (ref "J1") (pin "34") (pinfunction "IO3_34") (pintype "bidirectional"))
      (node (ref "P2") (pin "2") (pinfunction "2_2") (pintype "passive"))
    )
    (net (code "22") (name "/RX2") (class "Default")
      (node (ref "J1") (pin "27") (pinfunction "IO16_27") (pintype "bidirectional"))
      (node (ref "R6") (pin "1") (pinfunction "1_1") (pintype "passive"))
      (node (ref "U1") (pin "1") (pinfunction "RO_1") (pintype "output"))
    )
    (net (code "23") (name "/SCL") (class "Default")
      (node (ref "J1") (pin "36") (pinfunction "IO22_36") (pintype "bidirectional"))
      (node (ref "Q1") (pin "2") (pinfunction "S_2") (pintype "passive"))
      (node (ref "R14") (pin "1") (pinfunction "1_1") (pintype "passive"))
    )
    (net (code "24") (name "/SCL1") (class "Default")
      (node (ref "P1") (pin "4") (pinfunction "4_4") (pintype "passive"))
      (node (ref "Q1") (pin "3") (pinfunction "D_3") (pintype "passive"))
      (node (ref "R15") (pin "1") (pinfunction "1_1") (pintype "passive"))
    )
    (net (code "25") (name "/SDA") (class "Default")
      (node (ref "J1") (pin "33") (pinfunction "IO21_33") (pintype "bidirectional"))
      (node (ref "Q2") (pin "2") (pinfunction "S_2") (pintype "passive"))
      (node (ref "R41") (pin "1") (pinfunction "1_1") (pintype "passive"))
    )
    (net (code "26") (name "/SDA1") (class "Default")
      (node (ref "P1") (pin "3") (pinfunction "3_3") (pintype "passive"))
      (node (ref "Q2") (pin "3") (pinfunction "D_3") (pintype "passive"))
      (node (ref "R42") (pin "1") (pinfunction "1_1") (pintype "passive"))
    )
    (net (code "27") (name "/TX0") (class "Default")
      (node (ref "J1") (pin "35") (pinfunction "IO1_35") (pintype "bidirectional"))
      (node (ref "P2") (pin "3") (pinfunction "3_3") (pintype "passive"))
    )
    (net (code "28") (name "/TX2") (class "Default")
      (node (ref "J1") (pin "28") (pinfunction "IO17_28") (pintype "bidirectional"))
      (node (ref "R4") (pin "1") (pinfunction "1_1") (pintype "passive"))
      (node (ref "U1") (pin "4") (pinfunction "DI_4") (pintype "input"))
    )
    (net (code "29") (name "/V1-L") (class "Default")
      (node (ref "J2") (pin "19") (pinfunction "19_19") (pintype "passive"))
      (node (ref "PS1") (pin "1") (pinfunction "AC1_1") (pintype "input"))
      (node (ref "R35") (pin "1") (pinfunction "1_1") (pintype "passive"))
      (node (ref "R7") (pin "1") (pinfunction "1_1") (pintype "passive"))
    )
    (net (code "30") (name "/V1-N") (class "Default")
      (node (ref "D2") (pin "C") (pinfunction "K_C") (pintype "passive"))
      (node (ref "J2") (pin "18") (pinfunction "18_18") (pintype "passive"))
      (node (ref "PS1") (pin "2") (pinfunction "AC2_2") (pintype "input"))
      (node (ref "T1") (pin "2") (pinfunction "2_2") (pintype "passive"))
    )
    (net (code "31") (name "/V2-L") (class "Default")
      (node (ref "J2") (pin "17") (pinfunction "17_17") (pintype "passive"))
      (node (ref "R18") (pin "1") (pinfunction "1_1") (pintype "passive"))
      (node (ref "R36") (pin "1") (pinfunction "1_1") (pintype "passive"))
    )
    (net (code "32") (name "/V2-N") (class "Default")
      (node (ref "D4") (pin "C") (pinfunction "K_C") (pintype "passive"))
      (node (ref "J2") (pin "16") (pinfunction "16_16") (pintype "passive"))
      (node (ref "T2") (pin "2") (pinfunction "2_2") (pintype "passive"))
    )
    (net (code "33") (name "/V3-L") (class "Default")
      (node (ref "J2") (pin "15") (pinfunction "15_15") (pintype "passive"))
      (node (ref "R25") (pin "1") (pinfunction "1_1") (pintype "passive"))
      (node (ref "R37") (pin "1") (pinfunction "1_1") (pintype "passive"))
    )
    (net (code "34") (name "/V3-N") (class "Default")
      (node (ref "D6") (pin "C") (pinfunction "K_C") (pintype "passive"))
      (node (ref "J2") (pin "14") (pinfunction "14_14") (pintype "passive"))
      (node (ref "T3") (pin "2") (pinfunction "2_2") (pintype "passive"))
    )
    (net (code "35") (name "/WIFI_RST") (class "Default")
      (node (ref "J1") (pin "30") (pinfunction "IO18_30") (pintype "bidirectional"))
      (node (ref "R32") (pin "1") (pinfunction "1_1") (pintype "passive"))
      (node (ref "SW1") (pin "1") (pinfunction "1_1") (pintype "passive"))
    )
    (net (code "36") (name "AGND") (class "Default")
      (node (ref "C11") (pin "1") (pinfunction "1_1") (pintype "passive"))
      (node (ref "C12") (pin "1") (pinfunction "1_1") (pintype "passive"))
      (node (ref "C3") (pin "1") (pinfunction "1_1") (pintype "passive"))
      (node (ref "C4") (pin "1") (pinfunction "1_1") (pintype "passive"))
      (node (ref "C7") (pin "1") (pinfunction "1_1") (pintype "passive"))
      (node (ref "C8") (pin "1") (pinfunction "1_1") (pintype "passive"))
      (node (ref "J2") (pin "11") (pinfunction "11_11") (pintype "passive"))
      (node (ref "J2") (pin "7") (pinfunction "7_7") (pintype "passive"))
      (node (ref "J2") (pin "9") (pinfunction "9_9") (pintype "passive"))
      (node (ref "R10") (pin "1") (pinfunction "1_1") (pintype "passive"))
      (node (ref "R11") (pin "1") (pinfunction "1_1") (pintype "passive"))
      (node (ref "R19") (pin "1") (pinfunction "1_1") (pintype "passive"))
      (node (ref "R21") (pin "1") (pinfunction "1_1") (pintype "passive"))
      (node (ref "R22") (pin "1") (pinfunction "1_1") (pintype "passive"))
      (node (ref "R28") (pin "1") (pinfunction "1_1") (pintype "passive"))
      (node (ref "R30") (pin "1") (pinfunction "1_1") (pintype "passive"))
      (node (ref "R31") (pin "1") (pinfunction "1_1") (pintype "passive"))
      (node (ref "R34") (pin "2") (pinfunction "2_2") (pintype "passive"))
      (node (ref "R8") (pin "1") (pinfunction "1_1") (pintype "passive"))
      (node (ref "SB1") (pin "2") (pinfunction "17_2") (pintype "passive"))
      (node (ref "SB2") (pin "2") (pinfunction "17_2") (pintype "passive"))
      (node (ref "SB3") (pin "2") (pinfunction "17_2") (pintype "passive"))
      (node (ref "T1") (pin "4") (pinfunction "4_4") (pintype "passive"))
      (node (ref "T2") (pin "4") (pinfunction "4_4") (pintype "passive"))
      (node (ref "T3") (pin "4") (pinfunction "4_4") (pintype "passive"))
    )
    (net (code "37") (name "GND") (class "Default")
      (node (ref "C13") (pin "2") (pinfunction "2_2") (pintype "passive"))
      (node (ref "C14") (pin "1") (pinfunction "1_1") (pintype "passive"))
      (node (ref "C15") (pin "1") (pinfunction "1_1") (pintype "passive"))
      (node (ref "J1") (pin "1") (pinfunction "GND@1_1") (pintype "bidirectional"))
      (node (ref "J1") (pin "15") (pinfunction "GND@15_15") (pintype "bidirectional"))
      (node (ref "J1") (pin "38") (pinfunction "GND@38_38") (pintype "bidirectional"))
      (node (ref "J1") (pin "GND@39") (pinfunction "THERMAL@39_GND@39") (pintype "bidirectional"))
      (node (ref "J1") (pin "GND@40") (pinfunction "THERMAL@39_GND@40") (pintype "bidirectional"))
      (node (ref "J1") (pin "GND@41") (pinfunction "THERMAL@39_GND@41") (pintype "bidirectional"))
      (node (ref "J1") (pin "GND@42") (pinfunction "THERMAL@39_GND@42") (pintype "bidirectional"))
      (node (ref "J1") (pin "GND@43") (pinfunction "THERMAL@39_GND@43") (pintype "bidirectional"))
      (node (ref "J1") (pin "GND@44") (pinfunction "THERMAL@39_GND@44") (pintype "bidirectional"))
      (node (ref "J1") (pin "GND@45") (pinfunction "THERMAL@39_GND@45") (pintype "bidirectional"))
      (node (ref "J1") (pin "GND@46") (pinfunction "THERMAL@39_GND@46") (pintype "bidirectional"))
      (node (ref "J1") (pin "GND@47") (pinfunction "THERMAL@39_GND@47") (pintype "bidirectional"))
      (node (ref "J2") (pin "1") (pinfunction "1_1") (pintype "passive"))
      (node (ref "P1") (pin "1") (pinfunction "1_1") (pintype "passive"))
      (node (ref "P2") (pin "1") (pinfunction "1_1") (pintype "passive"))
      (node (ref "P3") (pin "1") (pinfunction "1_1") (pintype "passive"))
      (node (ref "PS1") (pin "3") (pinfunction "-VO_3") (pintype "output"))
      (node (ref "R13") (pin "1") (pinfunction "1_1") (pintype "passive"))
      (node (ref "R34") (pin "1") (pinfunction "1_1") (pintype "passive"))
      (node (ref "SW1") (pin "2") (pinfunction "2_2") (pintype "passive"))
      (node (ref "U1") (pin "5") (pinfunction "GND_5") (pintype "power_in"))
      (node (ref "U2") (pin "1") (pinfunction "GND/ADJ_1") (pintype "power_in"))
    )
    (net (code "38") (name "Net-(C1-Pad2)") (class "Default")
      (node (ref "C1") (pin "2") (pinfunction "2_2") (pintype "passive"))
      (node (ref "R8") (pin "2") (pinfunction "2_2") (pintype "passive"))
      (node (ref "T1") (pin "3") (pinfunction "3_3") (pintype "passive"))
    )
    (net (code "39") (name "Net-(C5-Pad2)") (class "Default")
      (node (ref "C5") (pin "2") (pinfunction "2_2") (pintype "passive"))
      (node (ref "R19") (pin "2") (pinfunction "2_2") (pintype "passive"))
      (node (ref "T2") (pin "3") (pinfunction "3_3") (pintype "passive"))
    )
    (net (code "40") (name "Net-(C9-Pad2)") (class "Default")
      (node (ref "C9") (pin "2") (pinfunction "2_2") (pintype "passive"))
      (node (ref "R28") (pin "2") (pinfunction "2_2") (pintype "passive"))
      (node (ref "T3") (pin "3") (pinfunction "3_3") (pintype "passive"))
    )
    (net (code "41") (name "Net-(D1-PadA)") (class "Default")
      (node (ref "D1") (pin "A") (pinfunction "A_A") (pintype "passive"))
      (node (ref "R35") (pin "2") (pinfunction "2_2") (pintype "passive"))
    )
    (net (code "42") (name "Net-(D1-PadC)") (class "Default")
      (node (ref "D1") (pin "C") (pinfunction "C_C") (pintype "passive"))
      (node (ref "D2") (pin "A") (pinfunction "A_A") (pintype "passive"))
    )
    (net (code "43") (name "Net-(D3-PadA)") (class "Default")
      (node (ref "D3") (pin "A") (pinfunction "A_A") (pintype "passive"))
      (node (ref "R36") (pin "2") (pinfunction "2_2") (pintype "passive"))
    )
    (net (code "44") (name "Net-(D3-PadC)") (class "Default")
      (node (ref "D3") (pin "C") (pinfunction "C_C") (pintype "passive"))
      (node (ref "D4") (pin "A") (pinfunction "A_A") (pintype "passive"))
    )
    (net (code "45") (name "Net-(D5-PadA)") (class "Default")
      (node (ref "D5") (pin "A") (pinfunction "A_A") (pintype "passive"))
      (node (ref "R37") (pin "2") (pinfunction "2_2") (pintype "passive"))
    )
    (net (code "46") (name "Net-(D5-PadC)") (class "Default")
      (node (ref "D5") (pin "C") (pinfunction "C_C") (pintype "passive"))
      (node (ref "D6") (pin "A") (pinfunction "A_A") (pintype "passive"))
    )
    (net (code "47") (name "Net-(D7-PadA)") (class "Default")
      (node (ref "D7") (pin "A") (pinfunction "A_A") (pintype "passive"))
      (node (ref "R38") (pin "2") (pinfunction "2_2") (pintype "passive"))
    )
    (net (code "48") (name "Net-(D8-PadA)") (class "Default")
      (node (ref "D8") (pin "A") (pinfunction "A_A") (pintype "passive"))
      (node (ref "R39") (pin "2") (pinfunction "2_2") (pintype "passive"))
    )
    (net (code "49") (name "Net-(D9-PadA)") (class "Default")
      (node (ref "D9") (pin "A") (pinfunction "A_A") (pintype "passive"))
      (node (ref "R40") (pin "2") (pinfunction "2_2") (pintype "passive"))
    )
    (net (code "50") (name "Net-(R7-Pad2)") (class "Default")
      (node (ref "R7") (pin "2") (pinfunction "2_2") (pintype "passive"))
      (node (ref "T1") (pin "1") (pinfunction "1_1") (pintype "passive"))
    )
    (net (code "51") (name "Net-(R18-Pad2)") (class "Default")
      (node (ref "R18") (pin "2") (pinfunction "2_2") (pintype "passive"))
      (node (ref "T2") (pin "1") (pinfunction "1_1") (pintype "passive"))
    )
    (net (code "52") (name "Net-(R25-Pad2)") (class "Default")
      (node (ref "R25") (pin "2") (pinfunction "2_2") (pintype "passive"))
      (node (ref "T3") (pin "1") (pinfunction "1_1") (pintype "passive"))
    )
    (net (code "53") (name "Net-(SB1-16)") (class "Default")
      (node (ref "R9") (pin "1") (pinfunction "1_1") (pintype "passive"))
      (node (ref "SB1") (pin "1") (pinfunction "16_1") (pintype "passive"))
    )
    (net (code "54") (name "Net-(SB2-16)") (class "Default")
      (node (ref "R20") (pin "1") (pinfunction "1_1") (pintype "passive"))
      (node (ref "SB2") (pin "1") (pinfunction "16_1") (pintype "passive"))
    )
    (net (code "55") (name "Net-(SB3-16)") (class "Default")
      (node (ref "R29") (pin "1") (pinfunction "1_1") (pintype "passive"))
      (node (ref "SB3") (pin "1") (pinfunction "16_1") (pintype "passive"))
    )
    (net (code "56") (name "unconnected-(J1-IO2-Pad24)") (class "Default")
      (node (ref "J1") (pin "24") (pinfunction "IO2_24") (pintype "bidirectional"))
    )
    (net (code "57") (name "unconnected-(J1-IO5-Pad29)") (class "Default")
      (node (ref "J1") (pin "29") (pinfunction "IO5_29") (pintype "bidirectional"))
    )
    (net (code "58") (name "unconnected-(J1-IO12-Pad14)") (class "Default")
      (node (ref "J1") (pin "14") (pinfunction "IO12_14") (pintype "bidirectional"))
    )
    (net (code "59") (name "unconnected-(J1-IO13-Pad16)") (class "Default")
      (node (ref "J1") (pin "16") (pinfunction "IO13_16") (pintype "bidirectional"))
    )
    (net (code "60") (name "unconnected-(J1-IO14-Pad13)") (class "Default")
      (node (ref "J1") (pin "13") (pinfunction "IO14_13") (pintype "bidirectional"))
    )
    (net (code "61") (name "unconnected-(J1-IO15-Pad23)") (class "Default")
      (node (ref "J1") (pin "23") (pinfunction "IO15_23") (pintype "bidirectional"))
    )
    (net (code "62") (name "unconnected-(J1-IO23-Pad37)") (class "Default")
      (node (ref "J1") (pin "37") (pinfunction "IO23_37") (pintype "bidirectional"))
    )
    (net (code "63") (name "unconnected-(J1-NC@17-Pad17)") (class "Default")
      (node (ref "J1") (pin "17") (pinfunction "NC@17_17") (pintype "bidirectional"))
    )
    (net (code "64") (name "unconnected-(J1-NC@18-Pad18)") (class "Default")
      (node (ref "J1") (pin "18") (pinfunction "NC@18_18") (pintype "bidirectional"))
    )
    (net (code "65") (name "unconnected-(J1-NC@19-Pad19)") (class "Default")
      (node (ref "J1") (pin "19") (pinfunction "NC@19_19") (pintype "bidirectional"))
    )
    (net (code "66") (name "unconnected-(J1-NC@20-Pad20)") (class "Default")
      (node (ref "J1") (pin "20") (pinfunction "NC@20_20") (pintype "bidirectional"))
    )
    (net (code "67") (name "unconnected-(J1-NC@21-Pad21)") (class "Default")
      (node (ref "J1") (pin "21") (pinfunction "NC@21_21") (pintype "bidirectional"))
    )
    (net (code "68") (name "unconnected-(J1-NC@22-Pad22)") (class "Default")
      (node (ref "J1") (pin "22") (pinfunction "NC@22_22") (pintype "bidirectional"))
    )
    (net (code "69") (name "unconnected-(J1-NC@32-Pad32)") (class "Default")
      (node (ref "J1") (pin "32") (pinfunction "NC@32_32") (pintype "bidirectional"))
    )
    (net (code "70") (name "unconnected-(J2-Pad6)") (class "Default")
      (node (ref "J2") (pin "6") (pinfunction "6_6") (pintype "passive+no_connect"))
    )
    (net (code "71") (name "unconnected-(J2-Pad13)") (class "Default")
      (node (ref "J2") (pin "13") (pinfunction "13_13") (pintype "passive+no_connect"))
    )
    (net (code "72") (name "unconnected-(SW1-SHIELD-PadS1)") (class "Default")
      (node (ref "SW1") (pin "S1") (pinfunction "SHIELD_S1") (pintype "passive"))
    )
    (net (code "73") (name "unconnected-(SW1-SHIELD-PadS2)") (class "Default")
      (node (ref "SW1") (pin "S2") (pinfunction "SHIELD_S2") (pintype "passive"))
    )
  )
)
